# max14866.net
KiCad netlist of a schematic drawn in Altium Designer
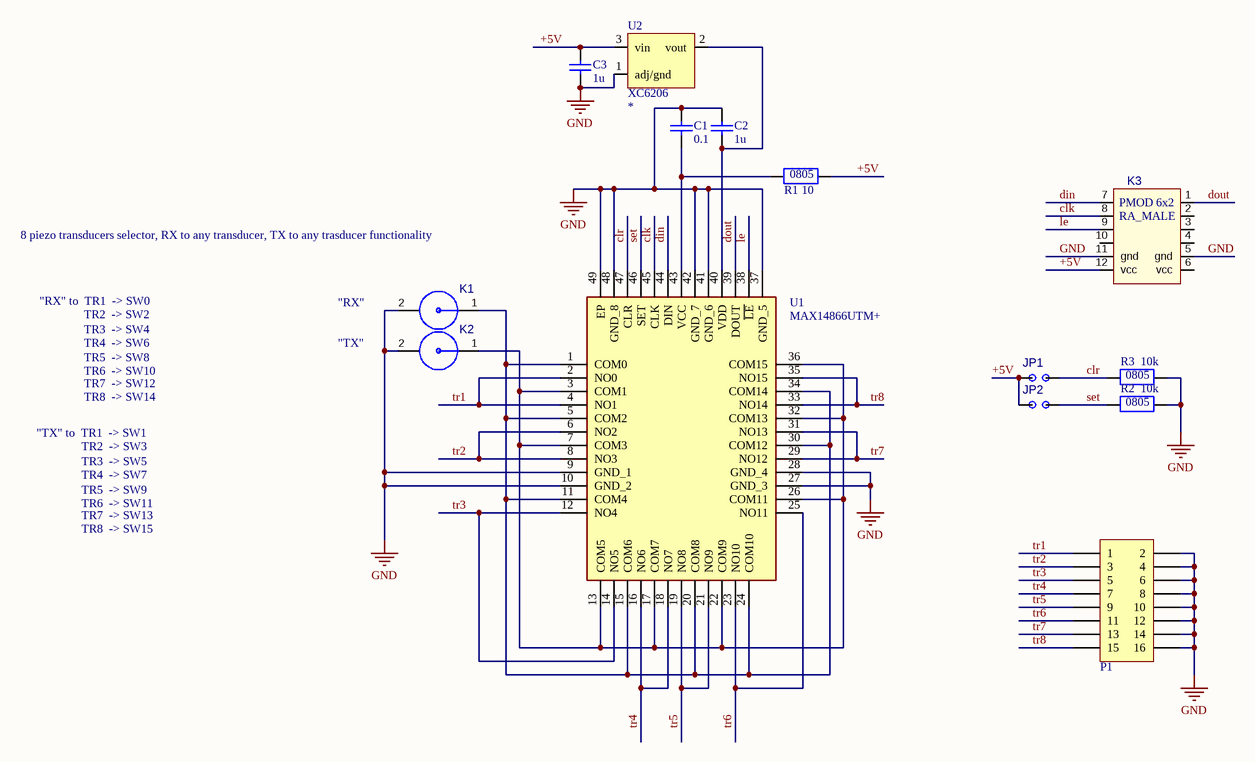
[diagram p0: max14866.SchDoc]

(export (version "E")
  (design (tool "Eeschema 10.0.6"))
  (components
    (comp (ref "C1")
      (value "0.1")
      (footprint "SM0805")
      (description "Capacitor")
      (fields (field (name "Comment") "cap0805") (field (name "PUBLISHER") "Altium Limited"))
      (libsource (lib "alt2017") (part "cap0805"))
    )
    (comp (ref "C2")
      (value "1u")
      (footprint "SM0805")
      (description "Capacitor")
      (fields (field (name "Comment") "cap0805") (field (name "PUBLISHER") "Altium Limited"))
      (libsource (lib "alt2017") (part "cap0805"))
    )
    (comp (ref "C3")
      (value "1u")
      (footprint "SM0805")
      (description "Capacitor")
      (fields (field (name "Comment") "cap0805") (field (name "PUBLISHER") "Altium Limited"))
      (libsource (lib "alt2017") (part "cap0805"))
    )
    (comp (ref "JP1") (value "JUMPER2") (footprint "JUMPER2") (libsource (lib "alt2017") (part "JUMPER2")))
    (comp (ref "JP2") (value "JUMPER2") (footprint "JUMPER2") (libsource (lib "alt2017") (part "JUMPER2")))
    (comp (ref "K1")
      (value "SMA_MALE_FEMALE")
      (footprint "AMPHENOL_MALE _FEMALE")
      (libsource (lib "alt2017") (part "SMA_MALE_FEMALE"))
    )
    (comp (ref "K2")
      (value "SMA_MALE_FEMALE")
      (footprint "AMPHENOL_MALE _FEMALE")
      (libsource (lib "alt2017") (part "SMA_MALE_FEMALE"))
    )
    (comp (ref "K3")
      (value "PMOD_6x2_ra_male_mirrored")
      (footprint "PMOD_6x2_RA_MALE_MIRRORED")
      (description "PMOD_6x2_right_angle")
      (libsource (lib "alt2017") (part "PMOD_6x2_ra_male_mirrored"))
    )
    (comp (ref "P1")
      (value "2x8, 2.54mm vertical")
      (footprint "2x8 pin 2.54mm")
      (description "Header, 16-Pin")
      (fields (field (name "PUBLISHER") "Altium Limited"))
      (libsource (lib "alt2017") (part "2x8, 2.54mm, vertical"))
    )
    (comp (ref "R1")
      (value "10")
      (footprint "SM0805")
      (description "Resistor")
      (fields (field (name "Comment") "res0805_EU") (field (name "PUBLISHER") "Altium Limited"))
      (libsource (lib "alt2017") (part "res0805_EU"))
    )
    (comp (ref "R2")
      (value "10k")
      (footprint "SM0805")
      (description "Resistor")
      (fields (field (name "Comment") "res0805_EU") (field (name "PUBLISHER") "Altium Limited"))
      (libsource (lib "alt2017") (part "res0805_EU"))
    )
    (comp (ref "R3")
      (value "10k")
      (footprint "SM0805")
      (description "Resistor")
      (fields (field (name "Comment") "res0805_EU") (field (name "PUBLISHER") "Altium Limited"))
      (libsource (lib "alt2017") (part "res0805_EU"))
    )
    (comp (ref "U1")
      (value "MAX14866UTM+")
      (footprint "QFN50P700X700X80-49N")
      (description "Integrated Circuit")
      (fields (field (name "MOUSER PART NUMBER") "700-MAX14866UTM+"))
      (libsource (lib "alt2017") (part "MAX14866UTM+"))
    )
    (comp (ref "U2")
      (value "XC6206")
      (footprint "SOT-23")
      (description "SOT-23-3 ldo")
      (fields (field (name "ALTIUM_UNNAMED_1") "*"))
      (libsource (lib "alt2017") (part "XC6206"))
    )
  )
  (nets
    (net (code "1") (name "/+5V") (class "Default")
      (node (ref "C3") (pin "2") (pinfunction "2_2") (pintype "passive"))
      (node (ref "JP1") (pin "2") (pinfunction "2_2") (pintype "passive"))
      (node (ref "JP2") (pin "2") (pinfunction "2_2") (pintype "passive"))
      (node (ref "K3") (pin "12") (pinfunction "vcc_12") (pintype "passive"))
      (node (ref "R1") (pin "2") (pinfunction "2_2") (pintype "passive"))
      (node (ref "U2") (pin "3") (pinfunction "vin_3") (pintype "passive"))
    )
    (net (code "2") (name "/clk") (class "Default")
      (node (ref "K3") (pin "8") (pinfunction "8_8") (pintype "passive"))
      (node (ref "U1") (pin "45") (pinfunction "CLK_45") (pintype "passive"))
    )
    (net (code "3") (name "/clr") (class "Default")
      (node (ref "JP1") (pin "1") (pinfunction "1_1") (pintype "passive"))
      (node (ref "R3") (pin "1") (pinfunction "1_1") (pintype "passive"))
      (node (ref "U1") (pin "47") (pinfunction "CLR_47") (pintype "passive"))
    )
    (net (code "4") (name "/din") (class "Default")
      (node (ref "K3") (pin "7") (pinfunction "7_7") (pintype "passive"))
      (node (ref "U1") (pin "44") (pinfunction "DIN_44") (pintype "passive"))
    )
    (net (code "5") (name "/dout") (class "Default")
      (node (ref "K3") (pin "1") (pinfunction "1_1") (pintype "passive"))
      (node (ref "U1") (pin "39") (pinfunction "DOUT_39") (pintype "passive"))
    )
    (net (code "6") (name "/le") (class "Default")
      (node (ref "K3") (pin "9") (pinfunction "9_9") (pintype "passive"))
      (node (ref "U1") (pin "38") (pinfunction "~{LE}_38") (pintype "passive"))
    )
    (net (code "7") (name "/set") (class "Default")
      (node (ref "JP2") (pin "1") (pinfunction "1_1") (pintype "passive"))
      (node (ref "R2") (pin "1") (pinfunction "1_1") (pintype "passive"))
      (node (ref "U1") (pin "46") (pinfunction "SET_46") (pintype "passive"))
    )
    (net (code "8") (name "/tr1") (class "Default")
      (node (ref "P1") (pin "1") (pinfunction "1_1") (pintype "passive"))
      (node (ref "U1") (pin "2") (pinfunction "NO0_2") (pintype "passive"))
      (node (ref "U1") (pin "4") (pinfunction "NO1_4") (pintype "passive"))
    )
    (net (code "9") (name "/tr2") (class "Default")
      (node (ref "P1") (pin "3") (pinfunction "3_3") (pintype "passive"))
      (node (ref "U1") (pin "6") (pinfunction "NO2_6") (pintype "passive"))
      (node (ref "U1") (pin "8") (pinfunction "NO3_8") (pintype "passive"))
    )
    (net (code "10") (name "/tr3") (class "Default")
      (node (ref "P1") (pin "5") (pinfunction "5_5") (pintype "passive"))
      (node (ref "U1") (pin "12") (pinfunction "NO4_12") (pintype "passive"))
      (node (ref "U1") (pin "14") (pinfunction "NO5_14") (pintype "passive"))
    )
    (net (code "11") (name "/tr4") (class "Default")
      (node (ref "P1") (pin "7") (pinfunction "7_7") (pintype "passive"))
      (node (ref "U1") (pin "16") (pinfunction "NO6_16") (pintype "passive"))
      (node (ref "U1") (pin "18") (pinfunction "NO7_18") (pintype "passive"))
    )
    (net (code "12") (name "/tr5") (class "Default")
      (node (ref "P1") (pin "9") (pinfunction "9_9") (pintype "passive"))
      (node (ref "U1") (pin "19") (pinfunction "NO8_19") (pintype "passive"))
      (node (ref "U1") (pin "21") (pinfunction "NO9_21") (pintype "passive"))
    )
    (net (code "13") (name "/tr6") (class "Default")
      (node (ref "P1") (pin "11") (pinfunction "11_11") (pintype "passive"))
      (node (ref "U1") (pin "23") (pinfunction "NO10_23") (pintype "passive"))
      (node (ref "U1") (pin "25") (pinfunction "NO11_25") (pintype "passive"))
    )
    (net (code "14") (name "/tr7") (class "Default")
      (node (ref "P1") (pin "13") (pinfunction "13_13") (pintype "passive"))
      (node (ref "U1") (pin "29") (pinfunction "NO12_29") (pintype "passive"))
      (node (ref "U1") (pin "31") (pinfunction "NO13_31") (pintype "passive"))
    )
    (net (code "15") (name "/tr8") (class "Default")
      (node (ref "P1") (pin "15") (pinfunction "15_15") (pintype "passive"))
      (node (ref "U1") (pin "33") (pinfunction "NO14_33") (pintype "passive"))
      (node (ref "U1") (pin "35") (pinfunction "NO15_35") (pintype "passive"))
    )
    (net (code "16") (name "GND") (class "Default")
      (node (ref "C1") (pin "2") (pinfunction "2_2") (pintype "passive"))
      (node (ref "C2") (pin "2") (pinfunction "2_2") (pintype "passive"))
      (node (ref "C3") (pin "1") (pinfunction "1_1") (pintype "passive"))
      (node (ref "K1") (pin "2") (pinfunction "2_2") (pintype "passive"))
      (node (ref "K2") (pin "2") (pinfunction "2_2") (pintype "passive"))
      (node (ref "K3") (pin "11") (pinfunction "gnd_11") (pintype "passive"))
      (node (ref "K3") (pin "5") (pinfunction "gnd_5") (pintype "passive"))
      (node (ref "P1") (pin "10") (pinfunction "10_10") (pintype "passive"))
      (node (ref "P1") (pin "12") (pinfunction "12_12") (pintype "passive"))
      (node (ref "P1") (pin "14") (pinfunction "14_14") (pintype "passive"))
      (node (ref "P1") (pin "16") (pinfunction "16_16") (pintype "passive"))
      (node (ref "P1") (pin "2") (pinfunction "2_2") (pintype "passive"))
      (node (ref "P1") (pin "4") (pinfunction "4_4") (pintype "passive"))
      (node (ref "P1") (pin "6") (pinfunction "6_6") (pintype "passive"))
      (node (ref "P1") (pin "8") (pinfunction "8_8") (pintype "passive"))
      (node (ref "R2") (pin "2") (pinfunction "2_2") (pintype "passive"))
      (node (ref "R3") (pin "2") (pinfunction "2_2") (pintype "passive"))
      (node (ref "U1") (pin "10") (pinfunction "GND_2_10") (pintype "passive"))
      (node (ref "U1") (pin "27") (pinfunction "GND_3_27") (pintype "passive"))
      (node (ref "U1") (pin "28") (pinfunction "GND_4_28") (pintype "passive"))
      (node (ref "U1") (pin "37") (pinfunction "GND_5_37") (pintype "passive"))
      (node (ref "U1") (pin "41") (pinfunction "GND_6_41") (pintype "passive"))
      (node (ref "U1") (pin "42") (pinfunction "GND_7_42") (pintype "passive"))
      (node (ref "U1") (pin "48") (pinfunction "GND_8_48") (pintype "passive"))
      (node (ref "U1") (pin "49") (pinfunction "EP_49") (pintype "passive"))
      (node (ref "U1") (pin "9") (pinfunction "GND_1_9") (pintype "passive"))
      (node (ref "U2") (pin "1") (pinfunction "adj/gnd_1") (pintype "passive"))
    )
    (net (code "17") (name "Net-(U1-COM0)") (class "Default")
      (node (ref "K1") (pin "1") (pinfunction "1_1") (pintype "passive"))
      (node (ref "U1") (pin "1") (pinfunction "COM0_1") (pintype "passive"))
      (node (ref "U1") (pin "11") (pinfunction "COM4_11") (pintype "passive"))
      (node (ref "U1") (pin "15") (pinfunction "COM6_15") (pintype "passive"))
      (node (ref "U1") (pin "20") (pinfunction "COM8_20") (pintype "passive"))
      (node (ref "U1") (pin "24") (pinfunction "COM10_24") (pintype "passive"))
      (node (ref "U1") (pin "30") (pinfunction "COM12_30") (pintype "passive"))
      (node (ref "U1") (pin "34") (pinfunction "COM14_34") (pintype "passive"))
      (node (ref "U1") (pin "5") (pinfunction "COM2_5") (pintype "passive"))
    )
    (net (code "18") (name "Net-(U1-COM1)") (class "Default")
      (node (ref "K2") (pin "1") (pinfunction "1_1") (pintype "passive"))
      (node (ref "U1") (pin "13") (pinfunction "COM5_13") (pintype "passive"))
      (node (ref "U1") (pin "17") (pinfunction "COM7_17") (pintype "passive"))
      (node (ref "U1") (pin "22") (pinfunction "COM9_22") (pintype "passive"))
      (node (ref "U1") (pin "26") (pinfunction "COM11_26") (pintype "passive"))
      (node (ref "U1") (pin "3") (pinfunction "COM1_3") (pintype "passive"))
      (node (ref "U1") (pin "32") (pinfunction "COM13_32") (pintype "passive"))
      (node (ref "U1") (pin "36") (pinfunction "COM15_36") (pintype "passive"))
      (node (ref "U1") (pin "7") (pinfunction "COM3_7") (pintype "passive"))
    )
    (net (code "19") (name "Net-(U1-VCC)") (class "Default")
      (node (ref "C1") (pin "1") (pinfunction "1_1") (pintype "passive"))
      (node (ref "R1") (pin "1") (pinfunction "1_1") (pintype "passive"))
      (node (ref "U1") (pin "43") (pinfunction "VCC_43") (pintype "passive"))
    )
    (net (code "20") (name "Net-(U1-VDD)") (class "Default")
      (node (ref "C2") (pin "1") (pinfunction "1_1") (pintype "passive"))
      (node (ref "U1") (pin "40") (pinfunction "VDD_40") (pintype "passive"))
      (node (ref "U2") (pin "2") (pinfunction "vout_2") (pintype "passive"))
    )
    (net (code "21") (name "unconnected-(K3-Pad2)") (class "Default")
      (node (ref "K3") (pin "2") (pinfunction "2_2") (pintype "passive"))
    )
    (net (code "22") (name "unconnected-(K3-Pad3)") (class "Default")
      (node (ref "K3") (pin "3") (pinfunction "3_3") (pintype "passive"))
    )
    (net (code "23") (name "unconnected-(K3-Pad4)") (class "Default")
      (node (ref "K3") (pin "4") (pinfunction "4_4") (pintype "passive"))
    )
    (net (code "24") (name "unconnected-(K3-Pad10)") (class "Default")
      (node (ref "K3") (pin "10") (pinfunction "10_10") (pintype "passive"))
    )
    (net (code "25") (name "unconnected-(K3-vcc-Pad6)") (class "Default")
      (node (ref "K3") (pin "6") (pinfunction "vcc_6") (pintype "passive"))
    )
  )
)
